# Sheet1.net
KiCad netlist of a schematic drawn in Altium Designer
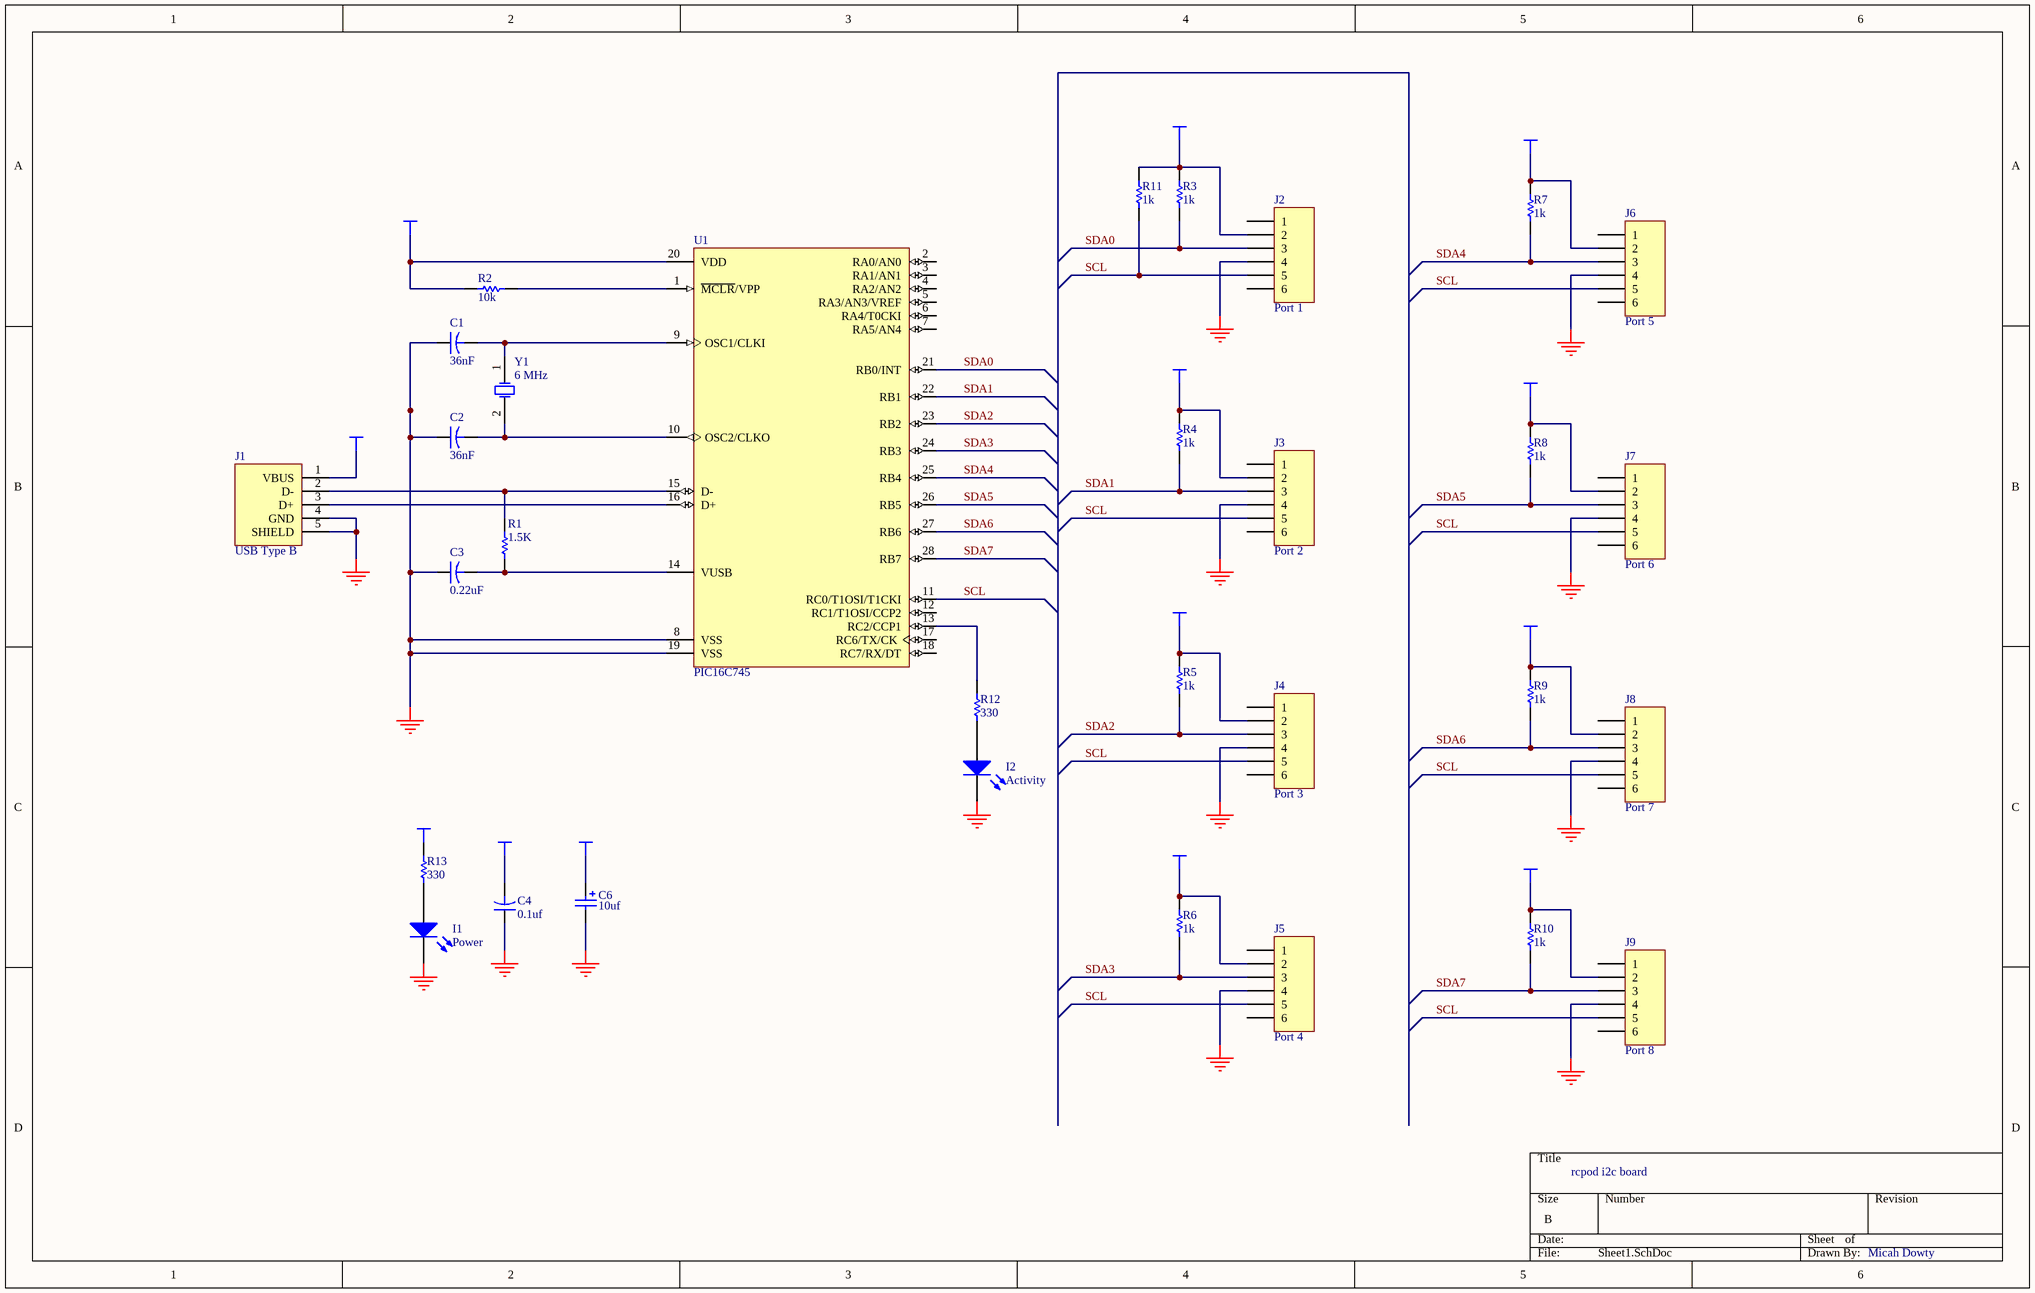
[diagram p0: Sheet1.SchDoc]

(export (version "E")
  (design (tool "Eeschema 10.0.6"))
  (components
    (comp (ref "C1")
      (value "Cap2")
      (footprint "CAPR5-4X5")
      (description "Capacitor")
      (fields
        (field (name "MANUFACTURER") "Generic Components")
        (field (name "ALTIUM_VALUE") "36nF")
        (field (name "PUBLISHER") "Altium Limited")
      )
      (libsource (lib "Miscellaneous Devices") (part "Cap2"))
    )
    (comp (ref "C2")
      (value "Cap2")
      (footprint "CAPR5-4X5")
      (description "Capacitor")
      (fields
        (field (name "MANUFACTURER") "Generic Components")
        (field (name "ALTIUM_VALUE") "36nF")
        (field (name "PUBLISHER") "Altium Limited")
      )
      (libsource (lib "Miscellaneous Devices") (part "Cap2"))
    )
    (comp (ref "C3")
      (value "0.22uF")
      (footprint "CAPR5-4X5")
      (description "Capacitor")
      (fields (field (name "MANUFACTURER") "Generic Components") (field (name "PUBLISHER") "Altium Limited"))
      (libsource (lib "Miscellaneous Devices") (part "Cap2"))
    )
    (comp (ref "C4")
      (value "0.1uf")
      (footprint "CAPR5-4X5")
      (description "Capacitor")
      (fields (field (name "MANUFACTURER") "Generic Components") (field (name "PUBLISHER") "Altium Limited"))
      (libsource (lib "Miscellaneous Devices") (part "Cap2"))
    )
    (comp (ref "C6")
      (value "Cap Pol1")
      (footprint "CAP-EE-1")
      (description "Polarized Capacitor (Radial)")
      (fields
        (field (name "MANUFACTURER") "Generic Components")
        (field (name "ALTIUM_VALUE") "10uf")
        (field (name "PUBLISHER") "Altium Limited")
      )
      (libsource (lib "Miscellaneous Devices") (part "Cap Pol1"))
    )
    (comp (ref "I1")
      (value "Power")
      (footprint "LED5MM")
      (description "Typical INFRARED GaAs LED")
      (fields (field (name "MANUFACTURER") "Generic Components") (field (name "PUBLISHER") "Altium Limited"))
      (libsource (lib "Miscellaneous Devices") (part "LED0"))
    )
    (comp (ref "I2")
      (value "Activity")
      (footprint "LED5MM")
      (description "Typical INFRARED GaAs LED")
      (fields (field (name "MANUFACTURER") "Generic Components") (field (name "PUBLISHER") "Altium Limited"))
      (libsource (lib "Miscellaneous Devices") (part "LED0"))
    )
    (comp (ref "J1")
      (value "USB")
      (footprint "USB-TYPEB")
      (description "Header, 4-Pin")
      (fields (field (name "MANUFACTURER") "Generic Components") (field (name "PUBLISHER") "Altium Limited"))
      (libsource (lib "parts") (part "USB Type B"))
    )
    (comp (ref "J2")
      (value "Port 1")
      (footprint "RJ11")
      (description "Header, 6-Pin")
      (fields (field (name "MANUFACTURER") "Generic Components") (field (name "PUBLISHER") "Altium Limited"))
      (libsource (lib "Miscellaneous Connectors") (part "Header 6"))
    )
    (comp (ref "J3")
      (value "Port 2")
      (footprint "RJ11")
      (description "Header, 6-Pin")
      (fields (field (name "MANUFACTURER") "Generic Components") (field (name "PUBLISHER") "Altium Limited"))
      (libsource (lib "Miscellaneous Connectors") (part "Header 6"))
    )
    (comp (ref "J4")
      (value "Port 3")
      (footprint "RJ11")
      (description "Header, 6-Pin")
      (fields (field (name "MANUFACTURER") "Generic Components") (field (name "PUBLISHER") "Altium Limited"))
      (libsource (lib "Miscellaneous Connectors") (part "Header 6"))
    )
    (comp (ref "J5")
      (value "Port 4")
      (footprint "RJ11")
      (description "Header, 6-Pin")
      (fields (field (name "MANUFACTURER") "Generic Components") (field (name "PUBLISHER") "Altium Limited"))
      (libsource (lib "Miscellaneous Connectors") (part "Header 6"))
    )
    (comp (ref "J6")
      (value "Port 5")
      (footprint "RJ11")
      (description "Header, 6-Pin")
      (fields (field (name "MANUFACTURER") "Generic Components") (field (name "PUBLISHER") "Altium Limited"))
      (libsource (lib "Miscellaneous Connectors") (part "Header 6"))
    )
    (comp (ref "J7")
      (value "Port 6")
      (footprint "RJ11")
      (description "Header, 6-Pin")
      (fields (field (name "MANUFACTURER") "Generic Components") (field (name "PUBLISHER") "Altium Limited"))
      (libsource (lib "Miscellaneous Connectors") (part "Header 6"))
    )
    (comp (ref "J8")
      (value "Port 7")
      (footprint "RJ11")
      (description "Header, 6-Pin")
      (fields (field (name "MANUFACTURER") "Generic Components") (field (name "PUBLISHER") "Altium Limited"))
      (libsource (lib "Miscellaneous Connectors") (part "Header 6"))
    )
    (comp (ref "J9")
      (value "Port 8")
      (footprint "RJ11")
      (description "Header, 6-Pin")
      (fields (field (name "MANUFACTURER") "Generic Components") (field (name "PUBLISHER") "Altium Limited"))
      (libsource (lib "Miscellaneous Connectors") (part "Header 6"))
    )
    (comp (ref "R1")
      (value "Res1")
      (footprint "AXIAL-0.3")
      (description "Resistor")
      (fields
        (field (name "MANUFACTURER") "Generic Components")
        (field (name "ALTIUM_VALUE") "1.5K")
        (field (name "PUBLISHER") "Altium Limited")
      )
      (libsource (lib "Miscellaneous Devices") (part "Res1"))
    )
    (comp (ref "R2")
      (value "Res1")
      (footprint "AXIAL-0.3")
      (description "Resistor")
      (fields
        (field (name "MANUFACTURER") "Generic Components")
        (field (name "ALTIUM_VALUE") "10k")
        (field (name "PUBLISHER") "Altium Limited")
      )
      (libsource (lib "Miscellaneous Devices") (part "Res1"))
    )
    (comp (ref "R3")
      (value "Res1")
      (footprint "AXIAL-0.3")
      (description "Resistor")
      (fields
        (field (name "MANUFACTURER") "Generic Components")
        (field (name "ALTIUM_VALUE") "1k")
        (field (name "PUBLISHER") "Altium Limited")
      )
      (libsource (lib "Miscellaneous Devices") (part "Res1"))
    )
    (comp (ref "R4")
      (value "Res1")
      (footprint "AXIAL-0.3")
      (description "Resistor")
      (fields
        (field (name "MANUFACTURER") "Generic Components")
        (field (name "ALTIUM_VALUE") "1k")
        (field (name "PUBLISHER") "Altium Limited")
      )
      (libsource (lib "Miscellaneous Devices") (part "Res1"))
    )
    (comp (ref "R5")
      (value "Res1")
      (footprint "AXIAL-0.3")
      (description "Resistor")
      (fields
        (field (name "MANUFACTURER") "Generic Components")
        (field (name "ALTIUM_VALUE") "1k")
        (field (name "PUBLISHER") "Altium Limited")
      )
      (libsource (lib "Miscellaneous Devices") (part "Res1"))
    )
    (comp (ref "R6")
      (value "Res1")
      (footprint "AXIAL-0.3")
      (description "Resistor")
      (fields
        (field (name "MANUFACTURER") "Generic Components")
        (field (name "ALTIUM_VALUE") "1k")
        (field (name "PUBLISHER") "Altium Limited")
      )
      (libsource (lib "Miscellaneous Devices") (part "Res1"))
    )
    (comp (ref "R7")
      (value "Res1")
      (footprint "AXIAL-0.3")
      (description "Resistor")
      (fields
        (field (name "MANUFACTURER") "Generic Components")
        (field (name "ALTIUM_VALUE") "1k")
        (field (name "PUBLISHER") "Altium Limited")
      )
      (libsource (lib "Miscellaneous Devices") (part "Res1"))
    )
    (comp (ref "R8")
      (value "Res1")
      (footprint "AXIAL-0.3")
      (description "Resistor")
      (fields
        (field (name "MANUFACTURER") "Generic Components")
        (field (name "ALTIUM_VALUE") "1k")
        (field (name "PUBLISHER") "Altium Limited")
      )
      (libsource (lib "Miscellaneous Devices") (part "Res1"))
    )
    (comp (ref "R9")
      (value "Res1")
      (footprint "AXIAL-0.3")
      (description "Resistor")
      (fields
        (field (name "MANUFACTURER") "Generic Components")
        (field (name "ALTIUM_VALUE") "1k")
        (field (name "PUBLISHER") "Altium Limited")
      )
      (libsource (lib "Miscellaneous Devices") (part "Res1"))
    )
    (comp (ref "R10")
      (value "Res1")
      (footprint "AXIAL-0.3")
      (description "Resistor")
      (fields
        (field (name "MANUFACTURER") "Generic Components")
        (field (name "ALTIUM_VALUE") "1k")
        (field (name "PUBLISHER") "Altium Limited")
      )
      (libsource (lib "Miscellaneous Devices") (part "Res1"))
    )
    (comp (ref "R11")
      (value "Res1")
      (footprint "AXIAL-0.3")
      (description "Resistor")
      (fields
        (field (name "MANUFACTURER") "Generic Components")
        (field (name "ALTIUM_VALUE") "1k")
        (field (name "PUBLISHER") "Altium Limited")
      )
      (libsource (lib "Miscellaneous Devices") (part "Res1"))
    )
    (comp (ref "R12")
      (value "Res1")
      (footprint "AXIAL-0.3")
      (description "Resistor")
      (fields
        (field (name "MANUFACTURER") "Generic Components")
        (field (name "ALTIUM_VALUE") "330")
        (field (name "PUBLISHER") "Altium Limited")
      )
      (libsource (lib "Miscellaneous Devices") (part "Res1"))
    )
    (comp (ref "R13")
      (value "Res1")
      (footprint "AXIAL-0.3")
      (description "Resistor")
      (fields
        (field (name "MANUFACTURER") "Generic Components")
        (field (name "ALTIUM_VALUE") "330")
        (field (name "PUBLISHER") "Altium Limited")
      )
      (libsource (lib "Miscellaneous Devices") (part "Res1"))
    )
    (comp (ref "U1")
      (value "~")
      (footprint "DIP-28")
      (description "EPROM-Based 8-Bit CMOS Microcontroller with USB")
      (fields (field (name "MANUFACTURER") "Microchip"))
      (libsource (lib "parts") (part "PIC16C745"))
    )
    (comp (ref "Y1")
      (value "6 MHz")
      (footprint "BCY-W2/E4.7")
      (description "Crystal Oscillator")
      (fields (field (name "MANUFACTURER") "Generic Components") (field (name "PUBLISHER") "Altium Limited"))
      (libsource (lib "Miscellaneous Devices") (part "XTAL"))
    )
  )
  (nets
    (net (code "1") (name "/SCL") (class "Default")
      (node (ref "J2") (pin "5") (pinfunction "5_5") (pintype "passive"))
      (node (ref "J3") (pin "5") (pinfunction "5_5") (pintype "passive"))
      (node (ref "J4") (pin "5") (pinfunction "5_5") (pintype "passive"))
      (node (ref "J5") (pin "5") (pinfunction "5_5") (pintype "passive"))
      (node (ref "J6") (pin "5") (pinfunction "5_5") (pintype "passive"))
      (node (ref "J7") (pin "5") (pinfunction "5_5") (pintype "passive"))
      (node (ref "J8") (pin "5") (pinfunction "5_5") (pintype "passive"))
      (node (ref "J9") (pin "5") (pinfunction "5_5") (pintype "passive"))
      (node (ref "R11") (pin "2") (pinfunction "2_2") (pintype "passive"))
      (node (ref "U1") (pin "11") (pinfunction "RC0/T1OSI/T1CKI_11") (pintype "bidirectional"))
    )
    (net (code "2") (name "/SDA0") (class "Default")
      (node (ref "J2") (pin "3") (pinfunction "3_3") (pintype "passive"))
      (node (ref "R3") (pin "2") (pinfunction "2_2") (pintype "passive"))
      (node (ref "U1") (pin "21") (pinfunction "RB0/INT_21") (pintype "bidirectional"))
    )
    (net (code "3") (name "/SDA1") (class "Default")
      (node (ref "J3") (pin "3") (pinfunction "3_3") (pintype "passive"))
      (node (ref "R4") (pin "2") (pinfunction "2_2") (pintype "passive"))
      (node (ref "U1") (pin "22") (pinfunction "RB1_22") (pintype "bidirectional"))
    )
    (net (code "4") (name "/SDA2") (class "Default")
      (node (ref "J4") (pin "3") (pinfunction "3_3") (pintype "passive"))
      (node (ref "R5") (pin "2") (pinfunction "2_2") (pintype "passive"))
      (node (ref "U1") (pin "23") (pinfunction "RB2_23") (pintype "bidirectional"))
    )
    (net (code "5") (name "/SDA3") (class "Default")
      (node (ref "J5") (pin "3") (pinfunction "3_3") (pintype "passive"))
      (node (ref "R6") (pin "2") (pinfunction "2_2") (pintype "passive"))
      (node (ref "U1") (pin "24") (pinfunction "RB3_24") (pintype "bidirectional"))
    )
    (net (code "6") (name "/SDA4") (class "Default")
      (node (ref "J6") (pin "3") (pinfunction "3_3") (pintype "passive"))
      (node (ref "R7") (pin "2") (pinfunction "2_2") (pintype "passive"))
      (node (ref "U1") (pin "25") (pinfunction "RB4_25") (pintype "bidirectional"))
    )
    (net (code "7") (name "/SDA5") (class "Default")
      (node (ref "J7") (pin "3") (pinfunction "3_3") (pintype "passive"))
      (node (ref "R8") (pin "2") (pinfunction "2_2") (pintype "passive"))
      (node (ref "U1") (pin "26") (pinfunction "RB5_26") (pintype "bidirectional"))
    )
    (net (code "8") (name "/SDA6") (class "Default")
      (node (ref "J8") (pin "3") (pinfunction "3_3") (pintype "passive"))
      (node (ref "R9") (pin "2") (pinfunction "2_2") (pintype "passive"))
      (node (ref "U1") (pin "27") (pinfunction "RB6_27") (pintype "bidirectional"))
    )
    (net (code "9") (name "/SDA7") (class "Default")
      (node (ref "J9") (pin "3") (pinfunction "3_3") (pintype "passive"))
      (node (ref "R10") (pin "2") (pinfunction "2_2") (pintype "passive"))
      (node (ref "U1") (pin "28") (pinfunction "RB7_28") (pintype "bidirectional"))
    )
    (net (code "10") (name "GND") (class "Default")
      (node (ref "C1") (pin "1") (pinfunction "1_1") (pintype "passive"))
      (node (ref "C2") (pin "1") (pinfunction "1_1") (pintype "passive"))
      (node (ref "C3") (pin "1") (pinfunction "1_1") (pintype "passive"))
      (node (ref "C4") (pin "1") (pinfunction "1_1") (pintype "passive"))
      (node (ref "C6") (pin "2") (pinfunction "2_2") (pintype "passive"))
      (node (ref "I1") (pin "2") (pinfunction "K_2") (pintype "passive"))
      (node (ref "I2") (pin "2") (pinfunction "K_2") (pintype "passive"))
      (node (ref "J1") (pin "4") (pinfunction "GND_4") (pintype "passive"))
      (node (ref "J1") (pin "5") (pinfunction "SHIELD_5") (pintype "power_in"))
      (node (ref "J2") (pin "4") (pinfunction "4_4") (pintype "passive"))
      (node (ref "J3") (pin "4") (pinfunction "4_4") (pintype "passive"))
      (node (ref "J4") (pin "4") (pinfunction "4_4") (pintype "passive"))
      (node (ref "J5") (pin "4") (pinfunction "4_4") (pintype "passive"))
      (node (ref "J6") (pin "4") (pinfunction "4_4") (pintype "passive"))
      (node (ref "J7") (pin "4") (pinfunction "4_4") (pintype "passive"))
      (node (ref "J8") (pin "4") (pinfunction "4_4") (pintype "passive"))
      (node (ref "J9") (pin "4") (pinfunction "4_4") (pintype "passive"))
      (node (ref "U1") (pin "19") (pinfunction "VSS_19") (pintype "power_in"))
      (node (ref "U1") (pin "8") (pinfunction "VSS_8") (pintype "power_in"))
    )
    (net (code "11") (name "Net-(I1-A)") (class "Default")
      (node (ref "I1") (pin "1") (pinfunction "A_1") (pintype "passive"))
      (node (ref "R13") (pin "2") (pinfunction "2_2") (pintype "passive"))
    )
    (net (code "12") (name "Net-(I2-A)") (class "Default")
      (node (ref "I2") (pin "1") (pinfunction "A_1") (pintype "passive"))
      (node (ref "R12") (pin "2") (pinfunction "2_2") (pintype "passive"))
    )
    (net (code "13") (name "Net-(J1-D+)") (class "Default")
      (node (ref "J1") (pin "3") (pinfunction "D+_3") (pintype "passive"))
      (node (ref "U1") (pin "16") (pinfunction "D+_16") (pintype "bidirectional"))
    )
    (net (code "14") (name "Net-(J1-D-)") (class "Default")
      (node (ref "J1") (pin "2") (pinfunction "D-_2") (pintype "passive"))
      (node (ref "R1") (pin "2") (pinfunction "2_2") (pintype "passive"))
      (node (ref "U1") (pin "15") (pinfunction "D-_15") (pintype "bidirectional"))
    )
    (net (code "15") (name "Net-(U1-OSC1{slash}CLKI)") (class "Default")
      (node (ref "C1") (pin "2") (pinfunction "2_2") (pintype "passive"))
      (node (ref "U1") (pin "9") (pinfunction "OSC1/CLKI_9") (pintype "input"))
      (node (ref "Y1") (pin "1") (pinfunction "OSC1_1") (pintype "passive"))
    )
    (net (code "16") (name "Net-(U1-OSC2{slash}CLKO)") (class "Default")
      (node (ref "C2") (pin "2") (pinfunction "2_2") (pintype "passive"))
      (node (ref "U1") (pin "10") (pinfunction "OSC2/CLKO_10") (pintype "output"))
      (node (ref "Y1") (pin "2") (pinfunction "OSC2_2") (pintype "passive"))
    )
    (net (code "17") (name "Net-(U1-RC2{slash}CCP1)") (class "Default")
      (node (ref "R12") (pin "1") (pinfunction "1_1") (pintype "passive"))
      (node (ref "U1") (pin "13") (pinfunction "RC2/CCP1_13") (pintype "bidirectional"))
    )
    (net (code "18") (name "Net-(U1-VUSB)") (class "Default")
      (node (ref "C3") (pin "2") (pinfunction "2_2") (pintype "passive"))
      (node (ref "R1") (pin "1") (pinfunction "1_1") (pintype "passive"))
      (node (ref "U1") (pin "14") (pinfunction "VUSB_14") (pintype "power_in"))
    )
    (net (code "19") (name "Net-(U1-~{MCLR}{slash}VPP)") (class "Default")
      (node (ref "R2") (pin "1") (pinfunction "1_1") (pintype "passive"))
      (node (ref "U1") (pin "1") (pinfunction "~{MCLR}/VPP_1") (pintype "input"))
    )
    (net (code "20") (name "VCC") (class "Default")
      (node (ref "C4") (pin "2") (pinfunction "2_2") (pintype "passive"))
      (node (ref "C6") (pin "1") (pinfunction "1_1") (pintype "passive"))
      (node (ref "J1") (pin "1") (pinfunction "VBUS_1") (pintype "passive"))
      (node (ref "J2") (pin "2") (pinfunction "2_2") (pintype "passive"))
      (node (ref "J3") (pin "2") (pinfunction "2_2") (pintype "passive"))
      (node (ref "J4") (pin "2") (pinfunction "2_2") (pintype "passive"))
      (node (ref "J5") (pin "2") (pinfunction "2_2") (pintype "passive"))
      (node (ref "J6") (pin "2") (pinfunction "2_2") (pintype "passive"))
      (node (ref "J7") (pin "2") (pinfunction "2_2") (pintype "passive"))
      (node (ref "J8") (pin "2") (pinfunction "2_2") (pintype "passive"))
      (node (ref "J9") (pin "2") (pinfunction "2_2") (pintype "passive"))
      (node (ref "R10") (pin "1") (pinfunction "1_1") (pintype "passive"))
      (node (ref "R11") (pin "1") (pinfunction "1_1") (pintype "passive"))
      (node (ref "R13") (pin "1") (pinfunction "1_1") (pintype "passive"))
      (node (ref "R2") (pin "2") (pinfunction "2_2") (pintype "passive"))
      (node (ref "R3") (pin "1") (pinfunction "1_1") (pintype "passive"))
      (node (ref "R4") (pin "1") (pinfunction "1_1") (pintype "passive"))
      (node (ref "R5") (pin "1") (pinfunction "1_1") (pintype "passive"))
      (node (ref "R6") (pin "1") (pinfunction "1_1") (pintype "passive"))
      (node (ref "R7") (pin "1") (pinfunction "1_1") (pintype "passive"))
      (node (ref "R8") (pin "1") (pinfunction "1_1") (pintype "passive"))
      (node (ref "R9") (pin "1") (pinfunction "1_1") (pintype "passive"))
      (node (ref "U1") (pin "20") (pinfunction "VDD_20") (pintype "power_in"))
    )
    (net (code "21") (name "unconnected-(J2-Pad1)") (class "Default")
      (node (ref "J2") (pin "1") (pinfunction "1_1") (pintype "passive"))
    )
    (net (code "22") (name "unconnected-(J2-Pad6)") (class "Default")
      (node (ref "J2") (pin "6") (pinfunction "6_6") (pintype "passive"))
    )
    (net (code "23") (name "unconnected-(J3-Pad1)") (class "Default")
      (node (ref "J3") (pin "1") (pinfunction "1_1") (pintype "passive"))
    )
    (net (code "24") (name "unconnected-(J3-Pad6)") (class "Default")
      (node (ref "J3") (pin "6") (pinfunction "6_6") (pintype "passive"))
    )
    (net (code "25") (name "unconnected-(J4-Pad1)") (class "Default")
      (node (ref "J4") (pin "1") (pinfunction "1_1") (pintype "passive"))
    )
    (net (code "26") (name "unconnected-(J4-Pad6)") (class "Default")
      (node (ref "J4") (pin "6") (pinfunction "6_6") (pintype "passive"))
    )
    (net (code "27") (name "unconnected-(J5-Pad1)") (class "Default")
      (node (ref "J5") (pin "1") (pinfunction "1_1") (pintype "passive"))
    )
    (net (code "28") (name "unconnected-(J5-Pad6)") (class "Default")
      (node (ref "J5") (pin "6") (pinfunction "6_6") (pintype "passive"))
    )
    (net (code "29") (name "unconnected-(J6-Pad1)") (class "Default")
      (node (ref "J6") (pin "1") (pinfunction "1_1") (pintype "passive"))
    )
    (net (code "30") (name "unconnected-(J6-Pad6)") (class "Default")
      (node (ref "J6") (pin "6") (pinfunction "6_6") (pintype "passive"))
    )
    (net (code "31") (name "unconnected-(J7-Pad1)") (class "Default")
      (node (ref "J7") (pin "1") (pinfunction "1_1") (pintype "passive"))
    )
    (net (code "32") (name "unconnected-(J7-Pad6)") (class "Default")
      (node (ref "J7") (pin "6") (pinfunction "6_6") (pintype "passive"))
    )
    (net (code "33") (name "unconnected-(J8-Pad1)") (class "Default")
      (node (ref "J8") (pin "1") (pinfunction "1_1") (pintype "passive"))
    )
    (net (code "34") (name "unconnected-(J8-Pad6)") (class "Default")
      (node (ref "J8") (pin "6") (pinfunction "6_6") (pintype "passive"))
    )
    (net (code "35") (name "unconnected-(J9-Pad1)") (class "Default")
      (node (ref "J9") (pin "1") (pinfunction "1_1") (pintype "passive"))
    )
    (net (code "36") (name "unconnected-(J9-Pad6)") (class "Default")
      (node (ref "J9") (pin "6") (pinfunction "6_6") (pintype "passive"))
    )
    (net (code "37") (name "unconnected-(U1-RA0{slash}AN0-Pad2)") (class "Default")
      (node (ref "U1") (pin "2") (pinfunction "RA0/AN0_2") (pintype "bidirectional"))
    )
    (net (code "38") (name "unconnected-(U1-RA1{slash}AN1-Pad3)") (class "Default")
      (node (ref "U1") (pin "3") (pinfunction "RA1/AN1_3") (pintype "bidirectional"))
    )
    (net (code "39") (name "unconnected-(U1-RA2{slash}AN2-Pad4)") (class "Default")
      (node (ref "U1") (pin "4") (pinfunction "RA2/AN2_4") (pintype "bidirectional"))
    )
    (net (code "40") (name "unconnected-(U1-RA3{slash}AN3{slash}VREF-Pad5)") (class "Default")
      (node (ref "U1") (pin "5") (pinfunction "RA3/AN3/VREF_5") (pintype "bidirectional"))
    )
    (net (code "41") (name "unconnected-(U1-RA4{slash}T0CKI-Pad6)") (class "Default")
      (node (ref "U1") (pin "6") (pinfunction "RA4/T0CKI_6") (pintype "bidirectional"))
    )
    (net (code "42") (name "unconnected-(U1-RA5{slash}AN4-Pad7)") (class "Default")
      (node (ref "U1") (pin "7") (pinfunction "RA5/AN4_7") (pintype "bidirectional"))
    )
    (net (code "43") (name "unconnected-(U1-RC1{slash}T1OSI{slash}CCP2-Pad12)") (class "Default")
      (node (ref "U1") (pin "12") (pinfunction "RC1/T1OSI/CCP2_12") (pintype "bidirectional"))
    )
    (net (code "44") (name "unconnected-(U1-RC6{slash}TX{slash}CK-Pad17)") (class "Default")
      (node (ref "U1") (pin "17") (pinfunction "RC6/TX/CK_17") (pintype "bidirectional"))
    )
    (net (code "45") (name "unconnected-(U1-RC7{slash}RX{slash}DT-Pad18)") (class "Default")
      (node (ref "U1") (pin "18") (pinfunction "RC7/RX/DT_18") (pintype "bidirectional"))
    )
  )
)
